# micro_transponder.net
KiCad netlist of a schematic drawn in EAGLE
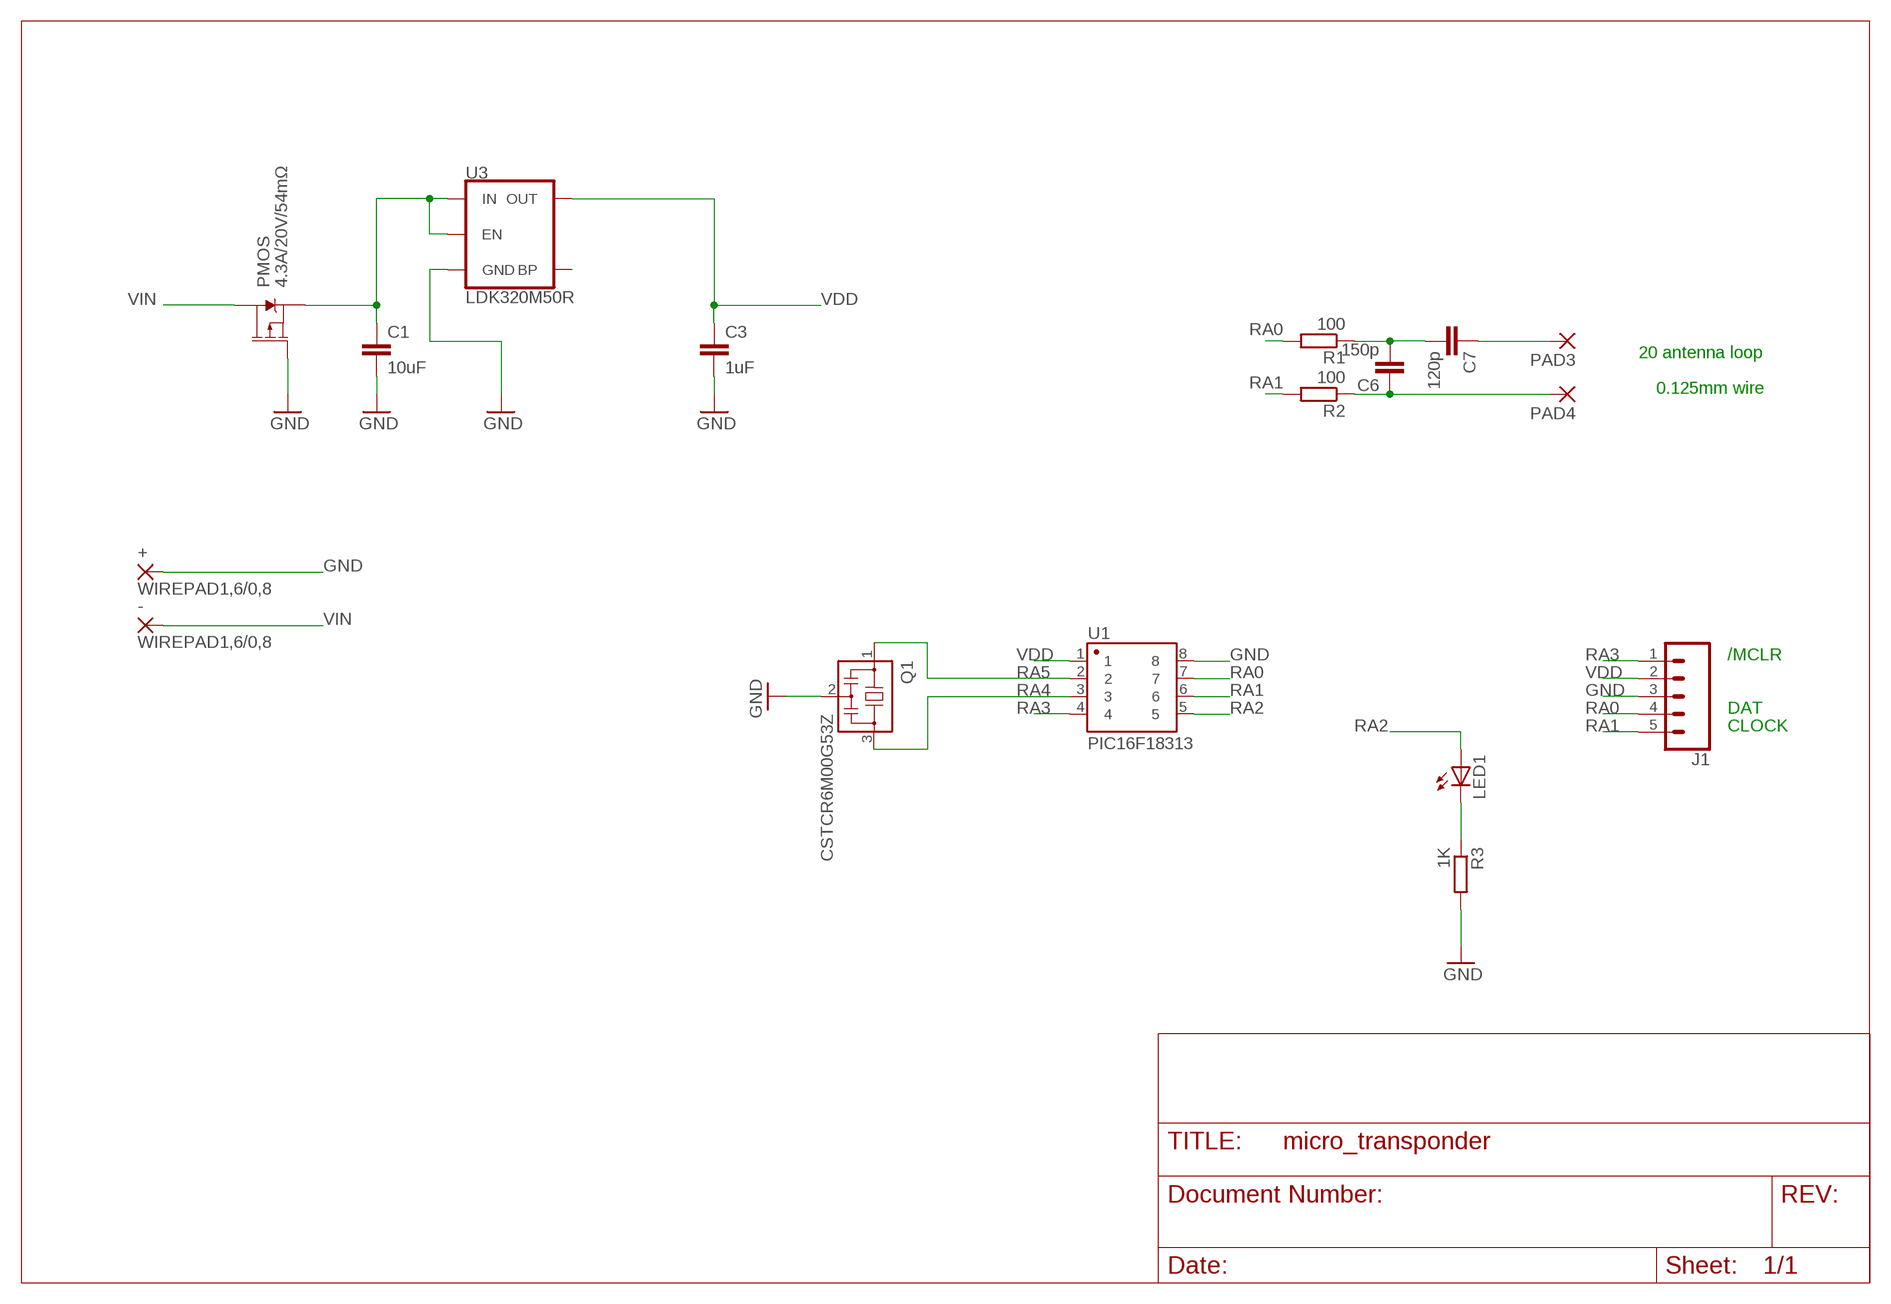
[diagram p0: schematic, sheet 1]

(export (version "E")
  (design (tool "Eeschema 10.0.6"))
  (components
    (comp (ref "+")
      (value "WIREPAD1,6/0,8")
      (footprint "eagle-import:1,6_0,8")
      (libsource (lib "eagle-import") (part "WIREPAD1,6/0,8"))
    )
    (comp (ref "-")
      (value "WIREPAD1,6/0,8")
      (footprint "eagle-import:1,6_0,8")
      (libsource (lib "eagle-import") (part "WIREPAD1,6/0,8"))
    )
    (comp (ref "C1")
      (value "10uF")
      (footprint "eagle-import:C0805")
      (libsource (lib "eagle-import") (part "C-EUC0805"))
    )
    (comp (ref "C3")
      (value "1uF")
      (footprint "eagle-import:C0603")
      (libsource (lib "eagle-import") (part "C-EUC0603"))
    )
    (comp (ref "C6")
      (value "150p")
      (footprint "eagle-import:C0603")
      (libsource (lib "eagle-import") (part "C-EUC0603"))
    )
    (comp (ref "C7")
      (value "120p")
      (footprint "eagle-import:C0603")
      (libsource (lib "eagle-import") (part "C-EUC0603"))
    )
    (comp (ref "J1")
      (value "CONN_051.27MM")
      (footprint "eagle-import:1X05_1.27MM")
      (libsource (lib "eagle-import") (part "CONN_051.27MM"))
    )
    (comp (ref "LED1")
      (value "LEDCHIP-LED0805")
      (footprint "eagle-import:CHIP-LED0805")
      (libsource (lib "eagle-import") (part "LEDCHIP-LED0805"))
    )
    (comp (ref "PAD3")
      (value "1,6/0,9")
      (footprint "eagle-import:1,6_0,9")
      (libsource (lib "eagle-import") (part "1,6/0,9"))
    )
    (comp (ref "PAD4")
      (value "1,6/0,9")
      (footprint "eagle-import:1,6_0,9")
      (libsource (lib "eagle-import") (part "1,6/0,9"))
    )
    (comp (ref "PMOS")
      (value "4.3A/20V/54mΩ")
      (footprint "eagle-import:SOT23-3")
      (libsource (lib "eagle-import") (part "MOSFET_PCH-IRLML2244"))
    )
    (comp (ref "Q1")
      (value "CSTCR6M00G53Z")
      (footprint "eagle-import:CSTCR6M")
      (fields (field (name "MPN") "CSTCR6M00G53-R0"))
      (libsource (lib "eagle-import") (part "CSTCR6M00G53Z"))
    )
    (comp (ref "R1")
      (value "100")
      (footprint "eagle-import:R0603")
      (libsource (lib "eagle-import") (part "R-EU_R0603"))
    )
    (comp (ref "R2")
      (value "100")
      (footprint "eagle-import:R0603")
      (libsource (lib "eagle-import") (part "R-EU_R0603"))
    )
    (comp (ref "R3")
      (value "1K")
      (footprint "eagle-import:R0603")
      (libsource (lib "eagle-import") (part "R-EU_R0603"))
    )
    (comp (ref "U1")
      (value "PIC16F18313")
      (footprint "eagle-import:SOIC8")
      (libsource (lib "eagle-import") (part "PIC16F18313"))
    )
    (comp (ref "U3")
      (value "LDK320M50R")
      (footprint "eagle-import:SOT23-5")
      (libsource (lib "eagle-import") (part "V_REG_MIC52055V"))
    )
  )
  (nets
    (net (code "1") (name "/RA0") (class "Default")
      (node (ref "J1") (pin "4") (pinfunction "4_4") (pintype "passive"))
      (node (ref "R1") (pin "2") (pinfunction "2_2") (pintype "passive"))
      (node (ref "U1") (pin "7") (pinfunction "7_7") (pintype "bidirectional"))
    )
    (net (code "2") (name "/RA1") (class "Default")
      (node (ref "J1") (pin "5") (pinfunction "5_5") (pintype "passive"))
      (node (ref "R2") (pin "2") (pinfunction "2_2") (pintype "passive"))
      (node (ref "U1") (pin "6") (pinfunction "6_6") (pintype "bidirectional"))
    )
    (net (code "3") (name "/RA2") (class "Default")
      (node (ref "LED1") (pin "A") (pinfunction "A_A") (pintype "passive"))
      (node (ref "U1") (pin "5") (pinfunction "5_5") (pintype "bidirectional"))
    )
    (net (code "4") (name "/RA3") (class "Default")
      (node (ref "J1") (pin "1") (pinfunction "1_1") (pintype "passive"))
      (node (ref "U1") (pin "4") (pinfunction "4_4") (pintype "bidirectional"))
    )
    (net (code "5") (name "/RA4") (class "Default")
      (node (ref "Q1") (pin "3") (pinfunction "3_3") (pintype "passive"))
      (node (ref "U1") (pin "3") (pinfunction "3_3") (pintype "bidirectional"))
    )
    (net (code "6") (name "/RA5") (class "Default")
      (node (ref "Q1") (pin "1") (pinfunction "1_1") (pintype "passive"))
      (node (ref "U1") (pin "2") (pinfunction "2_2") (pintype "bidirectional"))
    )
    (net (code "7") (name "/VDD") (class "Default")
      (node (ref "C3") (pin "1") (pinfunction "1_1") (pintype "passive"))
      (node (ref "J1") (pin "2") (pinfunction "2_2") (pintype "passive"))
      (node (ref "U1") (pin "1") (pinfunction "1_1") (pintype "bidirectional"))
      (node (ref "U3") (pin "5") (pinfunction "OUT_5") (pintype "passive"))
    )
    (net (code "8") (name "/VIN") (class "Default")
      (node (ref "-") (pin "1") (pinfunction "P_1") (pintype "passive"))
      (node (ref "PMOS") (pin "3") (pinfunction "D_3") (pintype "bidirectional"))
    )
    (net (code "9") (name "GND") (class "Default")
      (node (ref "+") (pin "1") (pinfunction "P_1") (pintype "passive"))
      (node (ref "C1") (pin "2") (pinfunction "2_2") (pintype "passive"))
      (node (ref "C3") (pin "2") (pinfunction "2_2") (pintype "passive"))
      (node (ref "J1") (pin "3") (pinfunction "3_3") (pintype "passive"))
      (node (ref "PMOS") (pin "1") (pinfunction "G_1") (pintype "bidirectional"))
      (node (ref "Q1") (pin "2") (pinfunction "2_2") (pintype "passive"))
      (node (ref "R3") (pin "2") (pinfunction "2_2") (pintype "passive"))
      (node (ref "U1") (pin "8") (pinfunction "8_8") (pintype "bidirectional"))
      (node (ref "U3") (pin "2") (pinfunction "GND_2") (pintype "input"))
    )
    (net (code "10") (name "Net-(C6-Pad2)") (class "Default")
      (node (ref "C6") (pin "2") (pinfunction "2_2") (pintype "passive"))
      (node (ref "C7") (pin "2") (pinfunction "2_2") (pintype "passive"))
      (node (ref "R1") (pin "1") (pinfunction "1_1") (pintype "passive"))
    )
    (net (code "11") (name "Net-(LED1-PadC)") (class "Default")
      (node (ref "LED1") (pin "C") (pinfunction "C_C") (pintype "passive"))
      (node (ref "R3") (pin "1") (pinfunction "1_1") (pintype "passive"))
    )
    (net (code "12") (name "Net-(PAD3-P)") (class "Default")
      (node (ref "C7") (pin "1") (pinfunction "1_1") (pintype "passive"))
      (node (ref "PAD3") (pin "1") (pinfunction "P_1") (pintype "passive"))
    )
    (net (code "13") (name "Net-(PAD4-P)") (class "Default")
      (node (ref "C6") (pin "1") (pinfunction "1_1") (pintype "passive"))
      (node (ref "PAD4") (pin "1") (pinfunction "P_1") (pintype "passive"))
      (node (ref "R2") (pin "1") (pinfunction "1_1") (pintype "passive"))
    )
    (net (code "14") (name "Net-(PMOS-S)") (class "Default")
      (node (ref "C1") (pin "1") (pinfunction "1_1") (pintype "passive"))
      (node (ref "PMOS") (pin "2") (pinfunction "S_2") (pintype "bidirectional"))
      (node (ref "U3") (pin "1") (pinfunction "IN_1") (pintype "input"))
      (node (ref "U3") (pin "3") (pinfunction "EN_3") (pintype "input"))
    )
    (net (code "15") (name "unconnected-(U3-BP-Pad4)") (class "Default")
      (node (ref "U3") (pin "4") (pinfunction "BP_4") (pintype "input"))
    )
  )
)
